# PICO_SDR.net
KiCad netlist of a schematic drawn in EAGLE
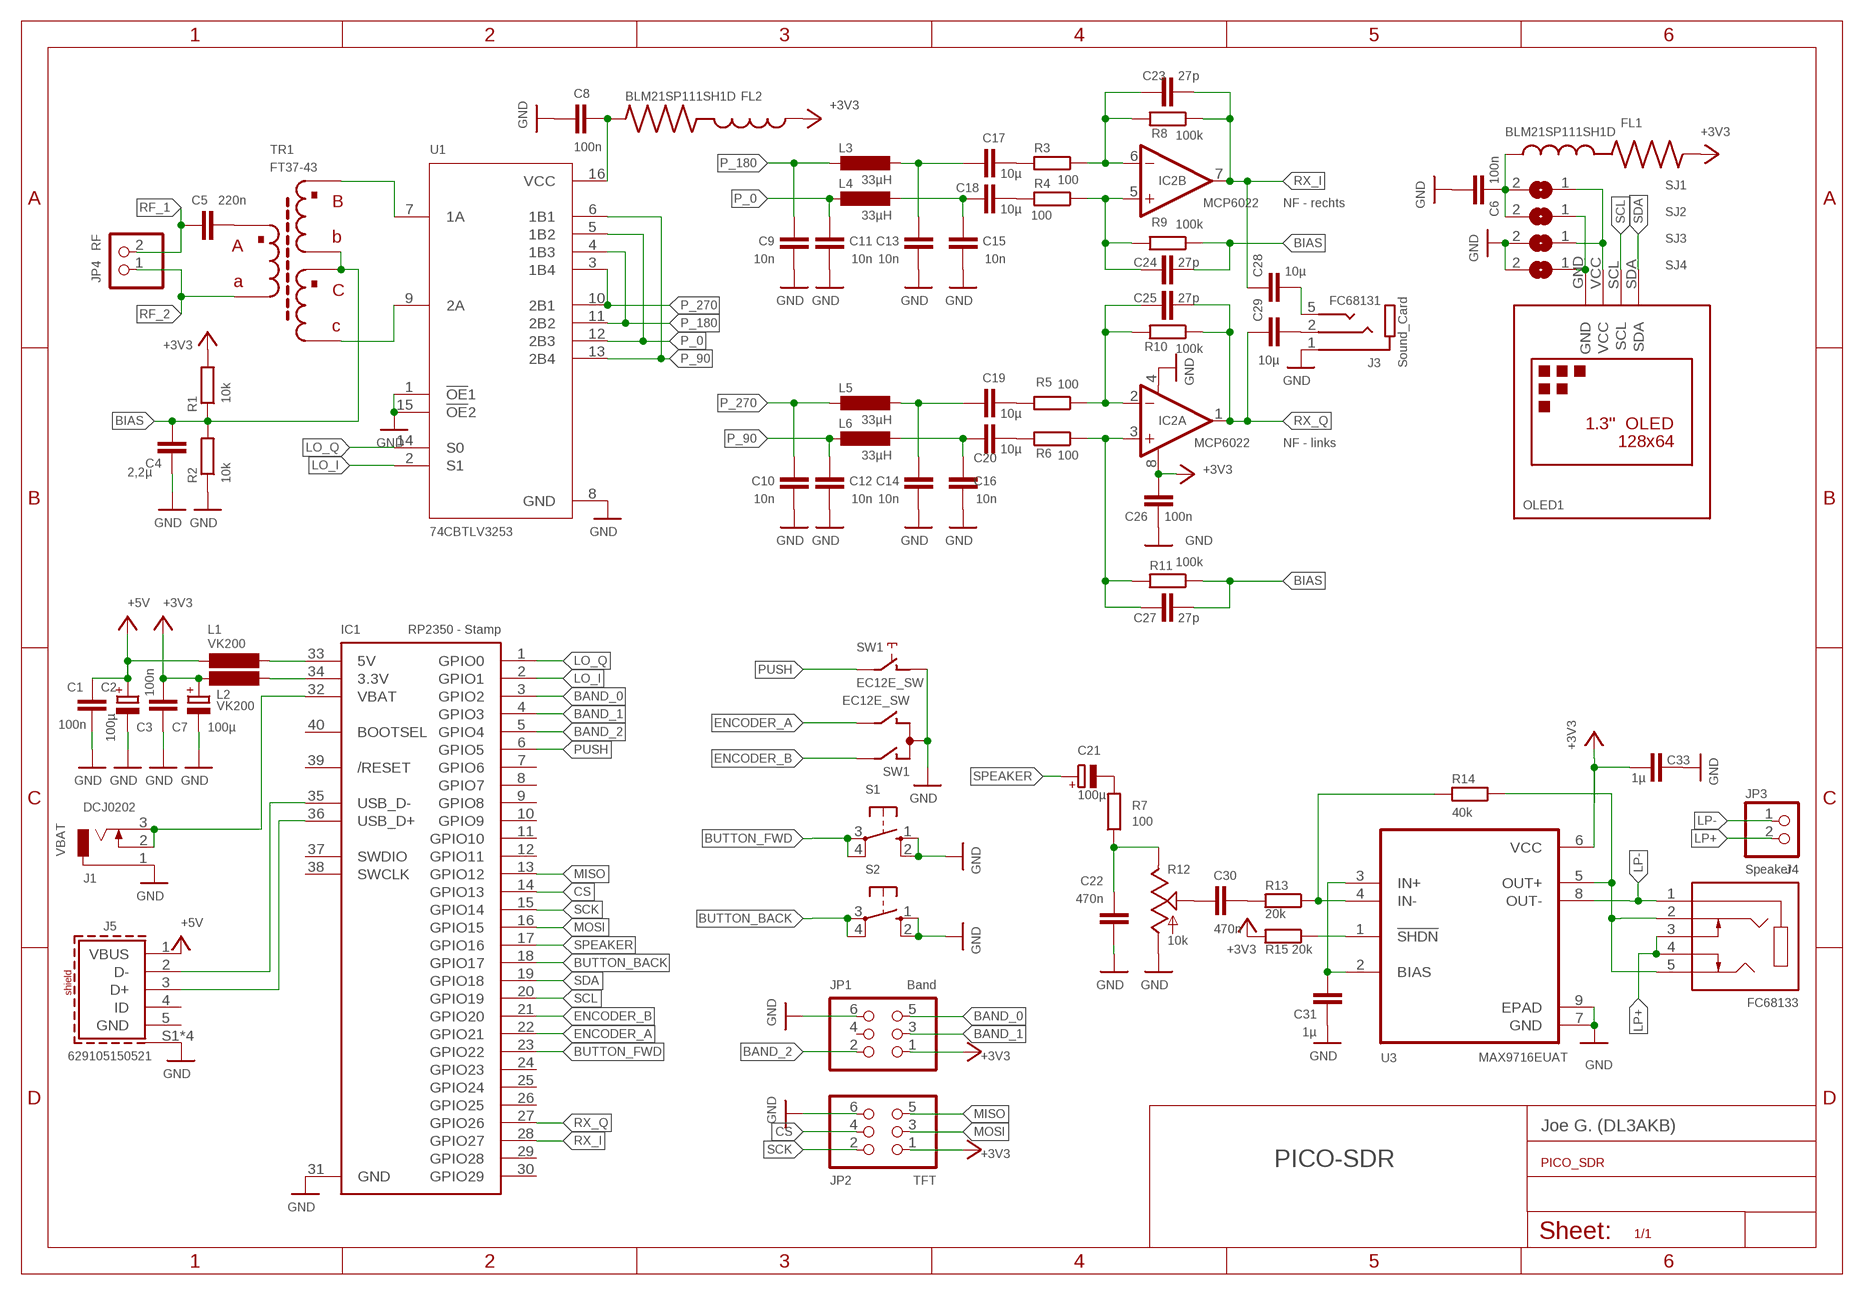
[diagram p0: schematic, sheet 1]

(export (version "E")
  (design (tool "Eeschema 10.0.6"))
  (components
    (comp (ref "C1")
      (value "100n")
      (footprint "eagle-import:C1206")
      (libsource (lib "eagle-import") (part "C-EUC1206"))
    )
    (comp (ref "C2")
      (value "100µ")
      (footprint "eagle-import:SMC_D")
      (libsource (lib "eagle-import") (part "CPOL-EUSMCD"))
    )
    (comp (ref "C3")
      (value "100n")
      (footprint "eagle-import:C1206")
      (libsource (lib "eagle-import") (part "C-EUC1206"))
    )
    (comp (ref "C4")
      (value "2,2µ")
      (footprint "eagle-import:C0805")
      (libsource (lib "eagle-import") (part "C-EUC0805"))
    )
    (comp (ref "C5")
      (value "220n")
      (footprint "eagle-import:C1206")
      (libsource (lib "eagle-import") (part "C-EUC1206"))
    )
    (comp (ref "C6")
      (value "100n")
      (footprint "eagle-import:C0805")
      (libsource (lib "eagle-import") (part "C-EUC0805"))
    )
    (comp (ref "C7")
      (value "100µ")
      (footprint "eagle-import:SMC_D")
      (libsource (lib "eagle-import") (part "CPOL-EUSMCD"))
    )
    (comp (ref "C8")
      (value "100n")
      (footprint "eagle-import:C0805")
      (libsource (lib "eagle-import") (part "C-EUC0805"))
    )
    (comp (ref "C9")
      (value "10n")
      (footprint "eagle-import:C0805")
      (libsource (lib "eagle-import") (part "C-EUC0805"))
    )
    (comp (ref "C10")
      (value "10n")
      (footprint "eagle-import:C0805")
      (libsource (lib "eagle-import") (part "C-EUC0805"))
    )
    (comp (ref "C11")
      (value "10n")
      (footprint "eagle-import:C0805")
      (libsource (lib "eagle-import") (part "C-EUC0805"))
    )
    (comp (ref "C12")
      (value "10n")
      (footprint "eagle-import:C0805")
      (libsource (lib "eagle-import") (part "C-EUC0805"))
    )
    (comp (ref "C13")
      (value "10n")
      (footprint "eagle-import:C0805")
      (libsource (lib "eagle-import") (part "C-EUC0805"))
    )
    (comp (ref "C14")
      (value "10n")
      (footprint "eagle-import:C0805")
      (libsource (lib "eagle-import") (part "C-EUC0805"))
    )
    (comp (ref "C15")
      (value "10n")
      (footprint "eagle-import:C0805")
      (libsource (lib "eagle-import") (part "C-EUC0805"))
    )
    (comp (ref "C16")
      (value "10n")
      (footprint "eagle-import:C0805")
      (libsource (lib "eagle-import") (part "C-EUC0805"))
    )
    (comp (ref "C17")
      (value "10µ")
      (footprint "eagle-import:C1206")
      (libsource (lib "eagle-import") (part "C-EUC1206"))
    )
    (comp (ref "C18")
      (value "10µ")
      (footprint "eagle-import:C1206")
      (libsource (lib "eagle-import") (part "C-EUC1206"))
    )
    (comp (ref "C19")
      (value "10µ")
      (footprint "eagle-import:C1206")
      (libsource (lib "eagle-import") (part "C-EUC1206"))
    )
    (comp (ref "C20")
      (value "10µ")
      (footprint "eagle-import:C1206")
      (libsource (lib "eagle-import") (part "C-EUC1206"))
    )
    (comp (ref "C21")
      (value "100µ")
      (footprint "eagle-import:SMC_D")
      (libsource (lib "eagle-import") (part "CPOL-EUSMCD"))
    )
    (comp (ref "C22")
      (value "470n")
      (footprint "eagle-import:C1206")
      (libsource (lib "eagle-import") (part "C-EUC1206"))
    )
    (comp (ref "C23")
      (value "27p")
      (footprint "eagle-import:C1206")
      (libsource (lib "eagle-import") (part "C-EUC1206"))
    )
    (comp (ref "C24")
      (value "27p")
      (footprint "eagle-import:C1206")
      (libsource (lib "eagle-import") (part "C-EUC1206"))
    )
    (comp (ref "C25")
      (value "27p")
      (footprint "eagle-import:C1206")
      (libsource (lib "eagle-import") (part "C-EUC1206"))
    )
    (comp (ref "C26")
      (value "100n")
      (footprint "eagle-import:C0805")
      (libsource (lib "eagle-import") (part "C-EUC0805"))
    )
    (comp (ref "C27")
      (value "27p")
      (footprint "eagle-import:C1206")
      (libsource (lib "eagle-import") (part "C-EUC1206"))
    )
    (comp (ref "C28")
      (value "10µ")
      (footprint "eagle-import:C1206")
      (libsource (lib "eagle-import") (part "C-EUC1206"))
    )
    (comp (ref "C29")
      (value "10µ")
      (footprint "eagle-import:C1206")
      (libsource (lib "eagle-import") (part "C-EUC1206"))
    )
    (comp (ref "C30")
      (value "470n")
      (footprint "eagle-import:C0805")
      (libsource (lib "eagle-import") (part "C-EUC0805"))
    )
    (comp (ref "C31")
      (value "1µ")
      (footprint "eagle-import:C0805")
      (libsource (lib "eagle-import") (part "C-EUC0805"))
    )
    (comp (ref "C33")
      (value "1µ")
      (footprint "eagle-import:C1206")
      (libsource (lib "eagle-import") (part "C-EUC1206"))
    )
    (comp (ref "FL1")
      (value "BLM21SP111SH1D")
      (footprint "eagle-import:BEADC2012X105N")
      (fields (field (name "MF") "Murata"))
      (libsource (lib "eagle-import") (part "BLM21SP111SH1D"))
    )
    (comp (ref "FL2")
      (value "BLM21SP111SH1D")
      (footprint "eagle-import:BEADC2012X105N")
      (fields (field (name "MF") "Murata"))
      (libsource (lib "eagle-import") (part "BLM21SP111SH1D"))
    )
    (comp (ref "IC1")
      (value "RP2350 - Stamp")
      (footprint "eagle-import:RP2XXX_STAMP_SMD")
      (libsource (lib "eagle-import") (part "RP2040_STAMPSMD"))
    )
    (comp (ref "IC2")
      (value "MCP6022")
      (footprint "eagle-import:SO08")
      (fields (field (name "MF") "TEXAS INSTRUMENTS") (field (name "MPN") "OPA2237UA"))
      (libsource (lib "eagle-import") (part "OPA2237U"))
    )
    (comp (ref "J1")
      (value "DCJ0202")
      (footprint "eagle-import:DCJ0202")
      (libsource (lib "eagle-import") (part "DCJ0202"))
    )
    (comp (ref "J3")
      (value "FC68131")
      (footprint "eagle-import:CLIFF_FC68131")
      (fields (field (name "MF") "Cliff"))
      (libsource (lib "eagle-import") (part "FC68131"))
    )
    (comp (ref "J4")
      (value "FC68133")
      (footprint "eagle-import:CLIFF_FC68133")
      (fields (field (name "MF") "Cliff"))
      (libsource (lib "eagle-import") (part "FC68133"))
    )
    (comp (ref "J5")
      (value "629105150521")
      (footprint "eagle-import:629105150521")
      (libsource (lib "eagle-import") (part "629105150521"))
    )
    (comp (ref "JP1")
      (value "Band")
      (footprint "eagle-import:2X03")
      (libsource (lib "eagle-import") (part "PINHD-2X3"))
    )
    (comp (ref "JP2")
      (value "TFT")
      (footprint "eagle-import:2X03")
      (libsource (lib "eagle-import") (part "PINHD-2X3"))
    )
    (comp (ref "JP3")
      (value "Speaker")
      (footprint "eagle-import:1X02")
      (libsource (lib "eagle-import") (part "PINHD-1X2"))
    )
    (comp (ref "JP4")
      (value "RF")
      (footprint "eagle-import:1X02")
      (libsource (lib "eagle-import") (part "PINHD-1X2"))
    )
    (comp (ref "L1")
      (value "VK200")
      (footprint "eagle-import:0207_5V")
      (libsource (lib "eagle-import") (part "L-EU0207/5V"))
    )
    (comp (ref "L2")
      (value "VK200")
      (footprint "eagle-import:0207_5V")
      (libsource (lib "eagle-import") (part "L-EU0207/5V"))
    )
    (comp (ref "L3")
      (value "33µH")
      (footprint "eagle-import:L1812")
      (libsource (lib "eagle-import") (part "rcl_334_L-EUL1812"))
    )
    (comp (ref "L4")
      (value "33µH")
      (footprint "eagle-import:L1812")
      (libsource (lib "eagle-import") (part "rcl_334_L-EUL1812"))
    )
    (comp (ref "L5")
      (value "33µH")
      (footprint "eagle-import:L1812")
      (libsource (lib "eagle-import") (part "rcl_334_L-EUL1812"))
    )
    (comp (ref "L6")
      (value "33µH")
      (footprint "eagle-import:L1812")
      (libsource (lib "eagle-import") (part "rcl_334_L-EUL1812"))
    )
    (comp (ref "OLED1")
      (value "OLED")
      (footprint "eagle-import:1.3")
      (libsource (lib "eagle-import") (part "OLED"))
    )
    (comp (ref "R1")
      (value "10k")
      (footprint "eagle-import:R0805")
      (libsource (lib "eagle-import") (part "R-EU_R0805"))
    )
    (comp (ref "R2")
      (value "10k")
      (footprint "eagle-import:R0805")
      (libsource (lib "eagle-import") (part "R-EU_R0805"))
    )
    (comp (ref "R3")
      (value "100")
      (footprint "eagle-import:R0805")
      (libsource (lib "eagle-import") (part "R-EU_R0805"))
    )
    (comp (ref "R4")
      (value "100")
      (footprint "eagle-import:R0805")
      (libsource (lib "eagle-import") (part "R-EU_R0805"))
    )
    (comp (ref "R5")
      (value "100")
      (footprint "eagle-import:R0805")
      (libsource (lib "eagle-import") (part "R-EU_R0805"))
    )
    (comp (ref "R6")
      (value "100")
      (footprint "eagle-import:R0805")
      (libsource (lib "eagle-import") (part "R-EU_R0805"))
    )
    (comp (ref "R7")
      (value "100")
      (footprint "eagle-import:R0805")
      (libsource (lib "eagle-import") (part "R-EU_R0805"))
    )
    (comp (ref "R8")
      (value "100k")
      (footprint "eagle-import:R0805")
      (libsource (lib "eagle-import") (part "R-EU_R0805"))
    )
    (comp (ref "R9")
      (value "100k")
      (footprint "eagle-import:R0805")
      (libsource (lib "eagle-import") (part "R-EU_R0805"))
    )
    (comp (ref "R10")
      (value "100k")
      (footprint "eagle-import:R0805")
      (libsource (lib "eagle-import") (part "R-EU_R0805"))
    )
    (comp (ref "R11")
      (value "100k")
      (footprint "eagle-import:R0805")
      (libsource (lib "eagle-import") (part "R-EU_R0805"))
    )
    (comp (ref "R12")
      (value "10k")
      (footprint "eagle-import:RK09K1130A6S")
      (fields (field (name "MF") "ALPS") (field (name "MP") "RK09K1130A6S"))
      (libsource (lib "eagle-import") (part "RK09K1130A6S"))
    )
    (comp (ref "R13")
      (value "20k")
      (footprint "eagle-import:R0805")
      (libsource (lib "eagle-import") (part "R-EU_R0805"))
    )
    (comp (ref "R14")
      (value "40k")
      (footprint "eagle-import:R0805")
      (libsource (lib "eagle-import") (part "R-EU_R0805"))
    )
    (comp (ref "R15")
      (value "20k")
      (footprint "eagle-import:R0805")
      (libsource (lib "eagle-import") (part "R-EU_R0805"))
    )
    (comp (ref "S1")
      (value "10-XX")
      (footprint "eagle-import:B3F-10XX")
      (fields (field (name "MPN") "B3F-1000"))
      (libsource (lib "eagle-import") (part "10-XX"))
    )
    (comp (ref "S2")
      (value "10-XX")
      (footprint "eagle-import:B3F-10XX")
      (fields (field (name "MPN") "B3F-1000"))
      (libsource (lib "eagle-import") (part "10-XX"))
    )
    (comp (ref "SJ1") (value "SJ") (footprint "eagle-import:SJ") (libsource (lib "eagle-import") (part "SJ")))
    (comp (ref "SJ2") (value "SJ") (footprint "eagle-import:SJ") (libsource (lib "eagle-import") (part "SJ")))
    (comp (ref "SJ3") (value "SJ") (footprint "eagle-import:SJ") (libsource (lib "eagle-import") (part "SJ")))
    (comp (ref "SJ4") (value "SJ") (footprint "eagle-import:SJ") (libsource (lib "eagle-import") (part "SJ")))
    (comp (ref "SW1")
      (value "EC12E_SW")
      (footprint "eagle-import:ALPS_EC12E_SW")
      (fields (field (name "MPN") "EC12E2424407"))
      (libsource (lib "eagle-import") (part "EC12E_SW"))
    )
    (comp (ref "TR1")
      (value "FT37-43")
      (footprint "eagle-import:FT37-43")
      (libsource (lib "eagle-import") (part "FT37-43"))
    )
    (comp (ref "U1")
      (value "74CBTLV3253")
      (footprint "eagle-import:SOIC127P599X175-16N")
      (fields (field (name "MF") "ON Semiconductor") (field (name "MP") "FST3253MX"))
      (libsource (lib "eagle-import") (part "FST3253MX"))
    )
    (comp (ref "U3")
      (value "MAX9716EUAT")
      (footprint "eagle-import:SOP65P490X110-9N")
      (fields (field (name "MF") "Analog Devices") (field (name "MP") "MAX9716EUA+"))
      (libsource (lib "eagle-import") (part "MAX9716EUAT"))
    )
  )
  (nets
    (net (code "1") (name "+3V3") (class "Default")
      (node (ref "C26") (pin "2") (pinfunction "2_2") (pintype "passive"))
      (node (ref "C3") (pin "2") (pinfunction "2_2") (pintype "passive"))
      (node (ref "C33") (pin "2") (pinfunction "2_2") (pintype "passive"))
      (node (ref "C7") (pin "+") (pinfunction "+_+") (pintype "passive"))
      (node (ref "FL1") (pin "2") (pinfunction "2_2") (pintype "passive"))
      (node (ref "FL2") (pin "1") (pinfunction "1_1") (pintype "passive"))
      (node (ref "IC2") (pin "8") (pinfunction "V+_8") (pintype "power_in"))
      (node (ref "JP1") (pin "1") (pinfunction "1_1") (pintype "passive"))
      (node (ref "JP2") (pin "1") (pinfunction "1_1") (pintype "passive"))
      (node (ref "L2") (pin "2") (pinfunction "2_2") (pintype "passive"))
      (node (ref "R1") (pin "2") (pinfunction "2_2") (pintype "passive"))
      (node (ref "R15") (pin "2") (pinfunction "2_2") (pintype "passive"))
      (node (ref "U3") (pin "6") (pinfunction "VCC_6") (pintype "power_in"))
    )
    (net (code "2") (name "+5V") (class "Default")
      (node (ref "C1") (pin "2") (pinfunction "2_2") (pintype "passive"))
      (node (ref "C2") (pin "+") (pinfunction "+_+") (pintype "passive"))
      (node (ref "J5") (pin "1") (pinfunction "VBUS_1") (pintype "passive"))
      (node (ref "L1") (pin "2") (pinfunction "2_2") (pintype "passive"))
    )
    (net (code "3") (name "/VBAT") (class "Default")
      (node (ref "IC1") (pin "32") (pinfunction "VBAT_32") (pintype "power_in"))
      (node (ref "J1") (pin "2") (pinfunction "2_2") (pintype "passive"))
      (node (ref "J1") (pin "3") (pinfunction "3_3") (pintype "passive"))
    )
    (net (code "4") (name "BAND_0") (class "Default")
      (node (ref "IC1") (pin "3") (pinfunction "GPIO2_3") (pintype "bidirectional"))
      (node (ref "JP1") (pin "5") (pinfunction "5_5") (pintype "passive"))
    )
    (net (code "5") (name "BAND_1") (class "Default")
      (node (ref "IC1") (pin "4") (pinfunction "GPIO3_4") (pintype "bidirectional"))
      (node (ref "JP1") (pin "3") (pinfunction "3_3") (pintype "passive"))
    )
    (net (code "6") (name "BAND_2") (class "Default")
      (node (ref "IC1") (pin "5") (pinfunction "GPIO4_5") (pintype "bidirectional"))
      (node (ref "JP1") (pin "2") (pinfunction "2_2") (pintype "passive"))
    )
    (net (code "7") (name "BIAS") (class "Default")
      (node (ref "C24") (pin "2") (pinfunction "2_2") (pintype "passive"))
      (node (ref "C27") (pin "2") (pinfunction "2_2") (pintype "passive"))
      (node (ref "C4") (pin "2") (pinfunction "2_2") (pintype "passive"))
      (node (ref "R1") (pin "1") (pinfunction "1_1") (pintype "passive"))
      (node (ref "R11") (pin "1") (pinfunction "1_1") (pintype "passive"))
      (node (ref "R2") (pin "2") (pinfunction "2_2") (pintype "passive"))
      (node (ref "R9") (pin "1") (pinfunction "1_1") (pintype "passive"))
      (node (ref "TR1") (pin "P$3") (pinfunction "P$5_P$3") (pintype "bidirectional"))
      (node (ref "TR1") (pin "P$5") (pinfunction "P$4_P$5") (pintype "bidirectional"))
    )
    (net (code "8") (name "BUTTON_BACK") (class "Default")
      (node (ref "IC1") (pin "18") (pinfunction "GPIO17_18") (pintype "bidirectional"))
      (node (ref "S2") (pin "3") (pinfunction "P_3") (pintype "passive"))
      (node (ref "S2") (pin "4") (pinfunction "P1_4") (pintype "passive"))
    )
    (net (code "9") (name "BUTTON_FWD") (class "Default")
      (node (ref "IC1") (pin "23") (pinfunction "GPIO22_23") (pintype "bidirectional"))
      (node (ref "S1") (pin "3") (pinfunction "P_3") (pintype "passive"))
      (node (ref "S1") (pin "4") (pinfunction "P1_4") (pintype "passive"))
    )
    (net (code "10") (name "CS") (class "Default")
      (node (ref "IC1") (pin "14") (pinfunction "GPIO13_14") (pintype "bidirectional"))
      (node (ref "JP2") (pin "4") (pinfunction "4_4") (pintype "passive"))
    )
    (net (code "11") (name "ENCODER_A") (class "Default")
      (node (ref "IC1") (pin "22") (pinfunction "GPIO21_22") (pintype "bidirectional"))
      (node (ref "SW1") (pin "B") (pinfunction "B_B") (pintype "passive"))
    )
    (net (code "12") (name "ENCODER_B") (class "Default")
      (node (ref "IC1") (pin "21") (pinfunction "GPIO20_21") (pintype "bidirectional"))
      (node (ref "SW1") (pin "A") (pinfunction "A_A") (pintype "passive"))
    )
    (net (code "13") (name "GND") (class "Default")
      (node (ref "C1") (pin "1") (pinfunction "1_1") (pintype "passive"))
      (node (ref "C10") (pin "1") (pinfunction "1_1") (pintype "passive"))
      (node (ref "C11") (pin "1") (pinfunction "1_1") (pintype "passive"))
      (node (ref "C12") (pin "1") (pinfunction "1_1") (pintype "passive"))
      (node (ref "C13") (pin "1") (pinfunction "1_1") (pintype "passive"))
      (node (ref "C14") (pin "1") (pinfunction "1_1") (pintype "passive"))
      (node (ref "C15") (pin "1") (pinfunction "1_1") (pintype "passive"))
      (node (ref "C16") (pin "1") (pinfunction "1_1") (pintype "passive"))
      (node (ref "C2") (pin "-") (pinfunction "-_-") (pintype "passive"))
      (node (ref "C22") (pin "1") (pinfunction "1_1") (pintype "passive"))
      (node (ref "C26") (pin "1") (pinfunction "1_1") (pintype "passive"))
      (node (ref "C3") (pin "1") (pinfunction "1_1") (pintype "passive"))
      (node (ref "C31") (pin "1") (pinfunction "1_1") (pintype "passive"))
      (node (ref "C33") (pin "1") (pinfunction "1_1") (pintype "passive"))
      (node (ref "C4") (pin "1") (pinfunction "1_1") (pintype "passive"))
      (node (ref "C6") (pin "2") (pinfunction "2_2") (pintype "passive"))
      (node (ref "C7") (pin "-") (pinfunction "-_-") (pintype "passive"))
      (node (ref "C8") (pin "2") (pinfunction "2_2") (pintype "passive"))
      (node (ref "C9") (pin "1") (pinfunction "1_1") (pintype "passive"))
      (node (ref "IC1") (pin "31") (pinfunction "GND_31") (pintype "power_in"))
      (node (ref "IC2") (pin "4") (pinfunction "V-_4") (pintype "power_in"))
      (node (ref "J1") (pin "1") (pinfunction "1_1") (pintype "passive"))
      (node (ref "J3") (pin "1") (pinfunction "SLEEVE_1") (pintype "passive"))
      (node (ref "J5") (pin "S1") (pinfunction "SHIELD_S1") (pintype "passive"))
      (node (ref "J5") (pin "S2") (pinfunction "SHIELD_S2") (pintype "passive"))
      (node (ref "J5") (pin "S3") (pinfunction "SHIELD_S3") (pintype "passive"))
      (node (ref "J5") (pin "S4") (pinfunction "SHIELD_S4") (pintype "passive"))
      (node (ref "JP1") (pin "6") (pinfunction "6_6") (pintype "passive"))
      (node (ref "JP2") (pin "6") (pinfunction "6_6") (pintype "passive"))
      (node (ref "R12") (pin "E") (pinfunction "3_E") (pintype "passive"))
      (node (ref "R2") (pin "1") (pinfunction "1_1") (pintype "passive"))
      (node (ref "S1") (pin "1") (pinfunction "S_1") (pintype "passive"))
      (node (ref "S1") (pin "2") (pinfunction "S1_2") (pintype "passive"))
      (node (ref "S2") (pin "1") (pinfunction "S_1") (pintype "passive"))
      (node (ref "S2") (pin "2") (pinfunction "S1_2") (pintype "passive"))
      (node (ref "SJ3") (pin "2") (pinfunction "2_2") (pintype "passive"))
      (node (ref "SJ4") (pin "2") (pinfunction "2_2") (pintype "passive"))
      (node (ref "SW1") (pin "C") (pinfunction "C_C") (pintype "passive"))
      (node (ref "SW1") (pin "D") (pinfunction "1_D") (pintype "passive"))
      (node (ref "U1") (pin "1") (pinfunction "~{OE}1_1") (pintype "input"))
      (node (ref "U1") (pin "15") (pinfunction "~{OE}2_15") (pintype "input"))
      (node (ref "U1") (pin "8") (pinfunction "GND_8") (pintype "power_in"))
      (node (ref "U3") (pin "7") (pinfunction "GND_7") (pintype "power_in"))
      (node (ref "U3") (pin "9") (pinfunction "EPAD_9") (pintype "power_in"))
    )
    (net (code "14") (name "LO_I") (class "Default")
      (node (ref "IC1") (pin "2") (pinfunction "GPIO1_2") (pintype "bidirectional"))
      (node (ref "U1") (pin "2") (pinfunction "S1_2") (pintype "input"))
    )
    (net (code "15") (name "LO_Q") (class "Default")
      (node (ref "IC1") (pin "1") (pinfunction "GPIO0_1") (pintype "bidirectional"))
      (node (ref "U1") (pin "14") (pinfunction "S0_14") (pintype "input"))
    )
    (net (code "16") (name "LP+") (class "Default")
      (node (ref "J4") (pin "3") (pinfunction "3_3") (pintype "passive"))
      (node (ref "J4") (pin "4") (pinfunction "4_4") (pintype "passive"))
      (node (ref "JP3") (pin "2") (pinfunction "2_2") (pintype "passive"))
    )
    (net (code "17") (name "LP-") (class "Default")
      (node (ref "J4") (pin "1") (pinfunction "1_1") (pintype "passive"))
      (node (ref "JP3") (pin "1") (pinfunction "1_1") (pintype "passive"))
      (node (ref "U3") (pin "8") (pinfunction "OUT-_8") (pintype "output"))
    )
    (net (code "18") (name "MISO") (class "Default")
      (node (ref "IC1") (pin "13") (pinfunction "GPIO12_13") (pintype "bidirectional"))
      (node (ref "JP2") (pin "5") (pinfunction "5_5") (pintype "passive"))
    )
    (net (code "19") (name "MOSI") (class "Default")
      (node (ref "IC1") (pin "16") (pinfunction "GPIO15_16") (pintype "bidirectional"))
      (node (ref "JP2") (pin "3") (pinfunction "3_3") (pintype "passive"))
    )
    (net (code "20") (name "Net-(C5-Pad2)") (class "Default")
      (node (ref "C5") (pin "2") (pinfunction "2_2") (pintype "passive"))
      (node (ref "TR1") (pin "P$1") (pinfunction "P$1_P$1") (pintype "bidirectional"))
    )
    (net (code "21") (name "Net-(C6-Pad1)") (class "Default")
      (node (ref "C6") (pin "1") (pinfunction "1_1") (pintype "passive"))
      (node (ref "FL1") (pin "1") (pinfunction "1_1") (pintype "passive"))
      (node (ref "SJ1") (pin "2") (pinfunction "2_2") (pintype "passive"))
      (node (ref "SJ2") (pin "2") (pinfunction "2_2") (pintype "passive"))
    )
    (net (code "22") (name "Net-(C13-Pad2)") (class "Default")
      (node (ref "C13") (pin "2") (pinfunction "2_2") (pintype "passive"))
      (node (ref "C17") (pin "1") (pinfunction "1_1") (pintype "passive"))
      (node (ref "L3") (pin "2") (pinfunction "2_2") (pintype "passive"))
    )
    (net (code "23") (name "Net-(C14-Pad2)") (class "Default")
      (node (ref "C14") (pin "2") (pinfunction "2_2") (pintype "passive"))
      (node (ref "C19") (pin "1") (pinfunction "1_1") (pintype "passive"))
      (node (ref "L5") (pin "2") (pinfunction "2_2") (pintype "passive"))
    )
    (net (code "24") (name "Net-(C15-Pad2)") (class "Default")
      (node (ref "C15") (pin "2") (pinfunction "2_2") (pintype "passive"))
      (node (ref "C18") (pin "1") (pinfunction "1_1") (pintype "passive"))
      (node (ref "L4") (pin "2") (pinfunction "2_2") (pintype "passive"))
    )
    (net (code "25") (name "Net-(C16-Pad2)") (class "Default")
      (node (ref "C16") (pin "2") (pinfunction "2_2") (pintype "passive"))
      (node (ref "C20") (pin "1") (pinfunction "1_1") (pintype "passive"))
      (node (ref "L6") (pin "2") (pinfunction "2_2") (pintype "passive"))
    )
    (net (code "26") (name "Net-(C17-Pad2)") (class "Default")
      (node (ref "C17") (pin "2") (pinfunction "2_2") (pintype "passive"))
      (node (ref "R3") (pin "2") (pinfunction "2_2") (pintype "passive"))
    )
    (net (code "27") (name "Net-(C18-Pad2)") (class "Default")
      (node (ref "C18") (pin "2") (pinfunction "2_2") (pintype "passive"))
      (node (ref "R4") (pin "2") (pinfunction "2_2") (pintype "passive"))
    )
    (net (code "28") (name "Net-(C19-Pad2)") (class "Default")
      (node (ref "C19") (pin "2") (pinfunction "2_2") (pintype "passive"))
      (node (ref "R5") (pin "2") (pinfunction "2_2") (pintype "passive"))
    )
    (net (code "29") (name "Net-(C20-Pad2)") (class "Default")
      (node (ref "C20") (pin "2") (pinfunction "2_2") (pintype "passive"))
      (node (ref "R6") (pin "2") (pinfunction "2_2") (pintype "passive"))
    )
    (net (code "30") (name "Net-(C21-Pad-)") (class "Default")
      (node (ref "C21") (pin "-") (pinfunction "-_-") (pintype "passive"))
      (node (ref "R7") (pin "2") (pinfunction "2_2") (pintype "passive"))
    )
    (net (code "31") (name "Net-(C30-Pad1)") (class "Default")
      (node (ref "C30") (pin "1") (pinfunction "1_1") (pintype "passive"))
      (node (ref "R13") (pin "2") (pinfunction "2_2") (pintype "passive"))
    )
    (net (code "32") (name "Net-(IC1-3.3V)") (class "Default")
      (node (ref "IC1") (pin "34") (pinfunction "3.3V_34") (pintype "power_in"))
      (node (ref "L2") (pin "1") (pinfunction "1_1") (pintype "passive"))
    )
    (net (code "33") (name "Net-(IC1-5V)") (class "Default")
      (node (ref "IC1") (pin "33") (pinfunction "5V_33") (pintype "power_in"))
      (node (ref "L1") (pin "1") (pinfunction "1_1") (pintype "passive"))
    )
    (net (code "34") (name "Net-(IC1-USB_D+)") (class "Default")
      (node (ref "IC1") (pin "36") (pinfunction "USB_D+_36") (pintype "bidirectional"))
      (node (ref "J5") (pin "3") (pinfunction "D+_3") (pintype "passive"))
    )
    (net (code "35") (name "Net-(IC1-USB_D-)") (class "Default")
      (node (ref "IC1") (pin "35") (pinfunction "USB_D-_35") (pintype "bidirectional"))
      (node (ref "J5") (pin "2") (pinfunction "D-_2") (pintype "passive"))
    )
    (net (code "36") (name "Net-(IC2A-+IN)") (class "Default")
      (node (ref "C27") (pin "1") (pinfunction "1_1") (pintype "passive"))
      (node (ref "IC2") (pin "3") (pinfunction "+IN_3") (pintype "input"))
      (node (ref "R11") (pin "2") (pinfunction "2_2") (pintype "passive"))
      (node (ref "R6") (pin "1") (pinfunction "1_1") (pintype "passive"))
    )
    (net (code "37") (name "Net-(IC2A--IN)") (class "Default")
      (node (ref "C25") (pin "1") (pinfunction "1_1") (pintype "passive"))
      (node (ref "IC2") (pin "2") (pinfunction "-IN_2") (pintype "input"))
      (node (ref "R10") (pin "2") (pinfunction "2_2") (pintype "passive"))
      (node (ref "R5") (pin "1") (pinfunction "1_1") (pintype "passive"))
    )
    (net (code "38") (name "Net-(IC2B-+IN)") (class "Default")
      (node (ref "C24") (pin "1") (pinfunction "1_1") (pintype "passive"))
      (node (ref "IC2") (pin "5") (pinfunction "+IN_5") (pintype "input"))
      (node (ref "R4") (pin "1") (pinfunction "1_1") (pintype "passive"))
      (node (ref "R9") (pin "2") (pinfunction "2_2") (pintype "passive"))
    )
    (net (code "39") (name "Net-(IC2B--IN)") (class "Default")
      (node (ref "C23") (pin "1") (pinfunction "1_1") (pintype "passive"))
      (node (ref "IC2") (pin "6") (pinfunction "-IN_6") (pintype "input"))
      (node (ref "R3") (pin "1") (pinfunction "1_1") (pintype "passive"))
      (node (ref "R8") (pin "2") (pinfunction "2_2") (pintype "passive"))
    )
    (net (code "40") (name "Net-(J3-RING)") (class "Default")
      (node (ref "C29") (pin "2") (pinfunction "2_2") (pintype "passive"))
      (node (ref "J3") (pin "2") (pinfunction "RING_2") (pintype "passive"))
    )
    (net (code "41") (name "Net-(J3-TIP)") (class "Default")
      (node (ref "C28") (pin "2") (pinfunction "2_2") (pintype "passive"))
      (node (ref "J3") (pin "5") (pinfunction "TIP_5") (pintype "passive"))
    )
    (net (code "42") (name "Net-(OLED1-PadGND)") (class "Default")
      (node (ref "OLED1") (pin "GND") (pinfunction "GND_GND") (pintype "bidirectional"))
      (node (ref "SJ2") (pin "1") (pinfunction "1_1") (pintype "passive"))
      (node (ref "SJ4") (pin "1") (pinfunction "1_1") (pintype "passive"))
    )
    (net (code "43") (name "Net-(OLED1-PadVCC)") (class "Default")
      (node (ref "OLED1") (pin "VCC") (pinfunction "VCC_VCC") (pintype "bidirectional"))
      (node (ref "SJ1") (pin "1") (pinfunction "1_1") (pintype "passive"))
      (node (ref "SJ3") (pin "1") (pinfunction "1_1") (pintype "passive"))
    )
    (net (code "44") (name "Net-(R12-1)") (class "Default")
      (node (ref "C22") (pin "2") (pinfunction "2_2") (pintype "passive"))
      (node (ref "R12") (pin "A") (pinfunction "1_A") (pintype "passive"))
      (node (ref "R7") (pin "1") (pinfunction "1_1") (pintype "passive"))
    )
    (net (code "45") (name "Net-(R12-2)") (class "Default")
      (node (ref "C30") (pin "2") (pinfunction "2_2") (pintype "passive"))
      (node (ref "R12") (pin "S") (pinfunction "2_S") (pintype "passive"))
    )
    (net (code "46") (name "Net-(TR1-P$3)") (class "Default")
      (node (ref "TR1") (pin "P$2") (pinfunction "P$3_P$2") (pintype "bidirectional"))
      (node (ref "U1") (pin "7") (pinfunction "1A_7") (pintype "bidirectional"))
    )
    (net (code "47") (name "Net-(U1-2A)") (class "Default")
      (node (ref "TR1") (pin "P$6") (pinfunction "P$6_P$6") (pintype "bidirectional"))
      (node (ref "U1") (pin "9") (pinfunction "2A_9") (pintype "bidirectional"))
    )
    (net (code "48") (name "Net-(U1-VCC)") (class "Default")
      (node (ref "C8") (pin "1") (pinfunction "1_1") (pintype "passive"))
      (node (ref "FL2") (pin "2") (pinfunction "2_2") (pintype "passive"))
      (node (ref "U1") (pin "16") (pinfunction "VCC_16") (pintype "power_in"))
    )
    (net (code "49") (name "Net-(U3-BIAS)") (class "Default")
      (node (ref "C31") (pin "2") (pinfunction "2_2") (pintype "passive"))
      (node (ref "U3") (pin "2") (pinfunction "BIAS_2") (pintype "bidirectional"))
      (node (ref "U3") (pin "3") (pinfunction "IN+_3") (pintype "input"))
    )
    (net (code "50") (name "Net-(U3-IN-)") (class "Default")
      (node (ref "R13") (pin "1") (pinfunction "1_1") (pintype "passive"))
      (node (ref "R14") (pin "2") (pinfunction "2_2") (pintype "passive"))
      (node (ref "U3") (pin "4") (pinfunction "IN-_4") (pintype "input"))
    )
    (net (code "51") (name "Net-(U3-OUT+)") (class "Default")
      (node (ref "J4") (pin "2") (pinfunction "2_2") (pintype "passive"))
      (node (ref "J4") (pin "5") (pinfunction "5_5") (pintype "passive"))
      (node (ref "R14") (pin "1") (pinfunction "1_1") (pintype "passive"))
      (node (ref "U3") (pin "5") (pinfunction "OUT+_5") (pintype "output"))
    )
    (net (code "52") (name "Net-(U3-~{SHDN})") (class "Default")
      (node (ref "R15") (pin "1") (pinfunction "1_1") (pintype "passive"))
      (node (ref "U3") (pin "1") (pinfunction "~{SHDN}_1") (pintype "bidirectional"))
    )
    (net (code "53") (name "PUSH") (class "Default")
      (node (ref "IC1") (pin "6") (pinfunction "GPIO5_6") (pintype "bidirectional"))
      (node (ref "SW1") (pin "E") (pinfunction "2_E") (pintype "passive"))
    )
    (net (code "54") (name "P_0") (class "Default")
      (node (ref "C11") (pin "2") (pinfunction "2_2") (pintype "passive"))
      (node (ref "L4") (pin "1") (pinfunction "1_1") (pintype "passive"))
      (node (ref "U1") (pin "12") (pinfunction "2B3_12") (pintype "bidirectional"))
      (node (ref "U1") (pin "5") (pinfunction "1B2_5") (pintype "bidirectional"))
    )
    (net (code "55") (name "P_90") (class "Default")
      (node (ref "C12") (pin "2") (pinfunction "2_2") (pintype "passive"))
      (node (ref "L6") (pin "1") (pinfunction "1_1") (pintype "passive"))
      (node (ref "U1") (pin "13") (pinfunction "2B4_13") (pintype "bidirectional"))
      (node (ref "U1") (pin "6") (pinfunction "1B1_6") (pintype "bidirectional"))
    )
    (net (code "56") (name "P_180") (class "Default")
      (node (ref "C9") (pin "2") (pinfunction "2_2") (pintype "passive"))
      (node (ref "L3") (pin "1") (pinfunction "1_1") (pintype "passive"))
      (node (ref "U1") (pin "11") (pinfunction "2B2_11") (pintype "bidirectional"))
      (node (ref "U1") (pin "4") (pinfunction "1B3_4") (pintype "bidirectional"))
    )
    (net (code "57") (name "P_270") (class "Default")
      (node (ref "C10") (pin "2") (pinfunction "2_2") (pintype "passive"))
      (node (ref "L5") (pin "1") (pinfunction "1_1") (pintype "passive"))
      (node (ref "U1") (pin "10") (pinfunction "2B1_10") (pintype "bidirectional"))
      (node (ref "U1") (pin "3") (pinfunction "1B4_3") (pintype "bidirectional"))
    )
    (net (code "58") (name "RF_1") (class "Default")
      (node (ref "C5") (pin "1") (pinfunction "1_1") (pintype "passive"))
      (node (ref "JP4") (pin "2") (pinfunction "2_2") (pintype "passive"))
    )
    (net (code "59") (name "RF_2") (class "Default")
      (node (ref "JP4") (pin "1") (pinfunction "1_1") (pintype "passive"))
      (node (ref "TR1") (pin "P$4") (pinfunction "P$2_P$4") (pintype "bidirectional"))
    )
    (net (code "60") (name "RX_I") (class "Default")
      (node (ref "C23") (pin "2") (pinfunction "2_2") (pintype "passive"))
      (node (ref "C28") (pin "1") (pinfunction "1_1") (pintype "passive"))
      (node (ref "IC1") (pin "28") (pinfunction "GPIO27_28") (pintype "bidirectional"))
      (node (ref "IC2") (pin "7") (pinfunction "OUT_7") (pintype "output"))
      (node (ref "R8") (pin "1") (pinfunction "1_1") (pintype "passive"))
    )
    (net (code "61") (name "RX_Q") (class "Default")
      (node (ref "C25") (pin "2") (pinfunction "2_2") (pintype "passive"))
      (node (ref "C29") (pin "1") (pinfunction "1_1") (pintype "passive"))
      (node (ref "IC1") (pin "27") (pinfunction "GPIO26_27") (pintype "bidirectional"))
      (node (ref "IC2") (pin "1") (pinfunction "OUT_1") (pintype "output"))
      (node (ref "R10") (pin "1") (pinfunction "1_1") (pintype "passive"))
    )
    (net (code "62") (name "SCK") (class "Default")
      (node (ref "IC1") (pin "15") (pinfunction "GPIO14_15") (pintype "bidirectional"))
      (node (ref "JP2") (pin "2") (pinfunction "2_2") (pintype "passive"))
    )
    (net (code "63") (name "SCL") (class "Default")
      (node (ref "IC1") (pin "20") (pinfunction "GPIO19_20") (pintype "bidirectional"))
      (node (ref "OLED1") (pin "SCL") (pinfunction "SCL_SCL") (pintype "bidirectional"))
    )
    (net (code "64") (name "SDA") (class "Default")
      (node (ref "IC1") (pin "19") (pinfunction "GPIO18_19") (pintype "bidirectional"))
      (node (ref "OLED1") (pin "SDA") (pinfunction "SDA_SDA") (pintype "bidirectional"))
    )
    (net (code "65") (name "SPEAKER") (class "Default")
      (node (ref "C21") (pin "+") (pinfunction "+_+") (pintype "passive"))
      (node (ref "IC1") (pin "17") (pinfunction "GPIO16_17") (pintype "bidirectional"))
    )
    (net (code "66") (name "unconnected-(IC1-BOOTSEL-Pad40)") (class "Default")
      (node (ref "IC1") (pin "40") (pinfunction "BOOTSEL_40") (pintype "input"))
    )
    (net (code "67") (name "unconnected-(IC1-GPIO6-Pad7)") (class "Default")
      (node (ref "IC1") (pin "7") (pinfunction "GPIO6_7") (pintype "bidirectional"))
    )
    (net (code "68") (name "unconnected-(IC1-GPIO7-Pad8)") (class "Default")
      (node (ref "IC1") (pin "8") (pinfunction "GPIO7_8") (pintype "bidirectional"))
    )
    (net (code "69") (name "unconnected-(IC1-GPIO8-Pad9)") (class "Default")
      (node (ref "IC1") (pin "9") (pinfunction "GPIO8_9") (pintype "bidirectional"))
    )
    (net (code "70") (name "unconnected-(IC1-GPIO9-Pad10)") (class "Default")
      (node (ref "IC1") (pin "10") (pinfunction "GPIO9_10") (pintype "bidirectional"))
    )
    (net (code "71") (name "unconnected-(IC1-GPIO10-Pad11)") (class "Default")
      (node (ref "IC1") (pin "11") (pinfunction "GPIO10_11") (pintype "bidirectional"))
    )
    (net (code "72") (name "unconnected-(IC1-GPIO11-Pad12)") (class "Default")
      (node (ref "IC1") (pin "12") (pinfunction "GPIO11_12") (pintype "bidirectional"))
    )
    (net (code "73") (name "unconnected-(IC1-GPIO23-Pad24)") (class "Default")
      (node (ref "IC1") (pin "24") (pinfunction "GPIO23_24") (pintype "bidirectional"))
    )
    (net (code "74") (name "unconnected-(IC1-GPIO24-Pad25)") (class "Default")
      (node (ref "IC1") (pin "25") (pinfunction "GPIO24_25") (pintype "bidirectional"))
    )
    (net (code "75") (name "unconnected-(IC1-GPIO25-Pad26)") (class "Default")
      (node (ref "IC1") (pin "26") (pinfunction "GPIO25_26") (pintype "bidirectional"))
    )
    (net (code "76") (name "unconnected-(IC1-GPIO28-Pad29)") (class "Default")
      (node (ref "IC1") (pin "29") (pinfunction "GPIO28_29") (pintype "bidirectional"))
    )
    (net (code "77") (name "unconnected-(IC1-GPIO29-Pad30)") (class "Default")
      (node (ref "IC1") (pin "30") (pinfunction "GPIO29_30") (pintype "bidirectional"))
    )
    (net (code "78") (name "unconnected-(IC1-SWCLK-Pad38)") (class "Default")
      (node (ref "IC1") (pin "38") (pinfunction "SWCLK_38") (pintype "input"))
    )
    (net (code "79") (name "unconnected-(IC1-SWDIO-Pad37)") (class "Default")
      (node (ref "IC1") (pin "37") (pinfunction "SWDIO_37") (pintype "bidirectional"))
    )
    (net (code "80") (name "unconnected-(IC1-{slash}RESET-Pad39)") (class "Default")
      (node (ref "IC1") (pin "39") (pinfunction "/RESET_39") (pintype "bidirectional"))
    )
    (net (code "81") (name "unconnected-(J5-GND-Pad5)") (class "Default")
      (node (ref "J5") (pin "5") (pinfunction "GND_5") (pintype "passive"))
    )
    (net (code "82") (name "unconnected-(J5-ID-Pad4)") (class "Default")
      (node (ref "J5") (pin "4") (pinfunction "ID_4") (pintype "passive"))
    )
    (net (code "83") (name "unconnected-(JP1-Pad4)") (class "Default")
      (node (ref "JP1") (pin "4") (pinfunction "4_4") (pintype "passive"))
    )
  )
)
